# Sheet1_MPU6050.net
KiCad netlist of a schematic drawn in Altium Designer
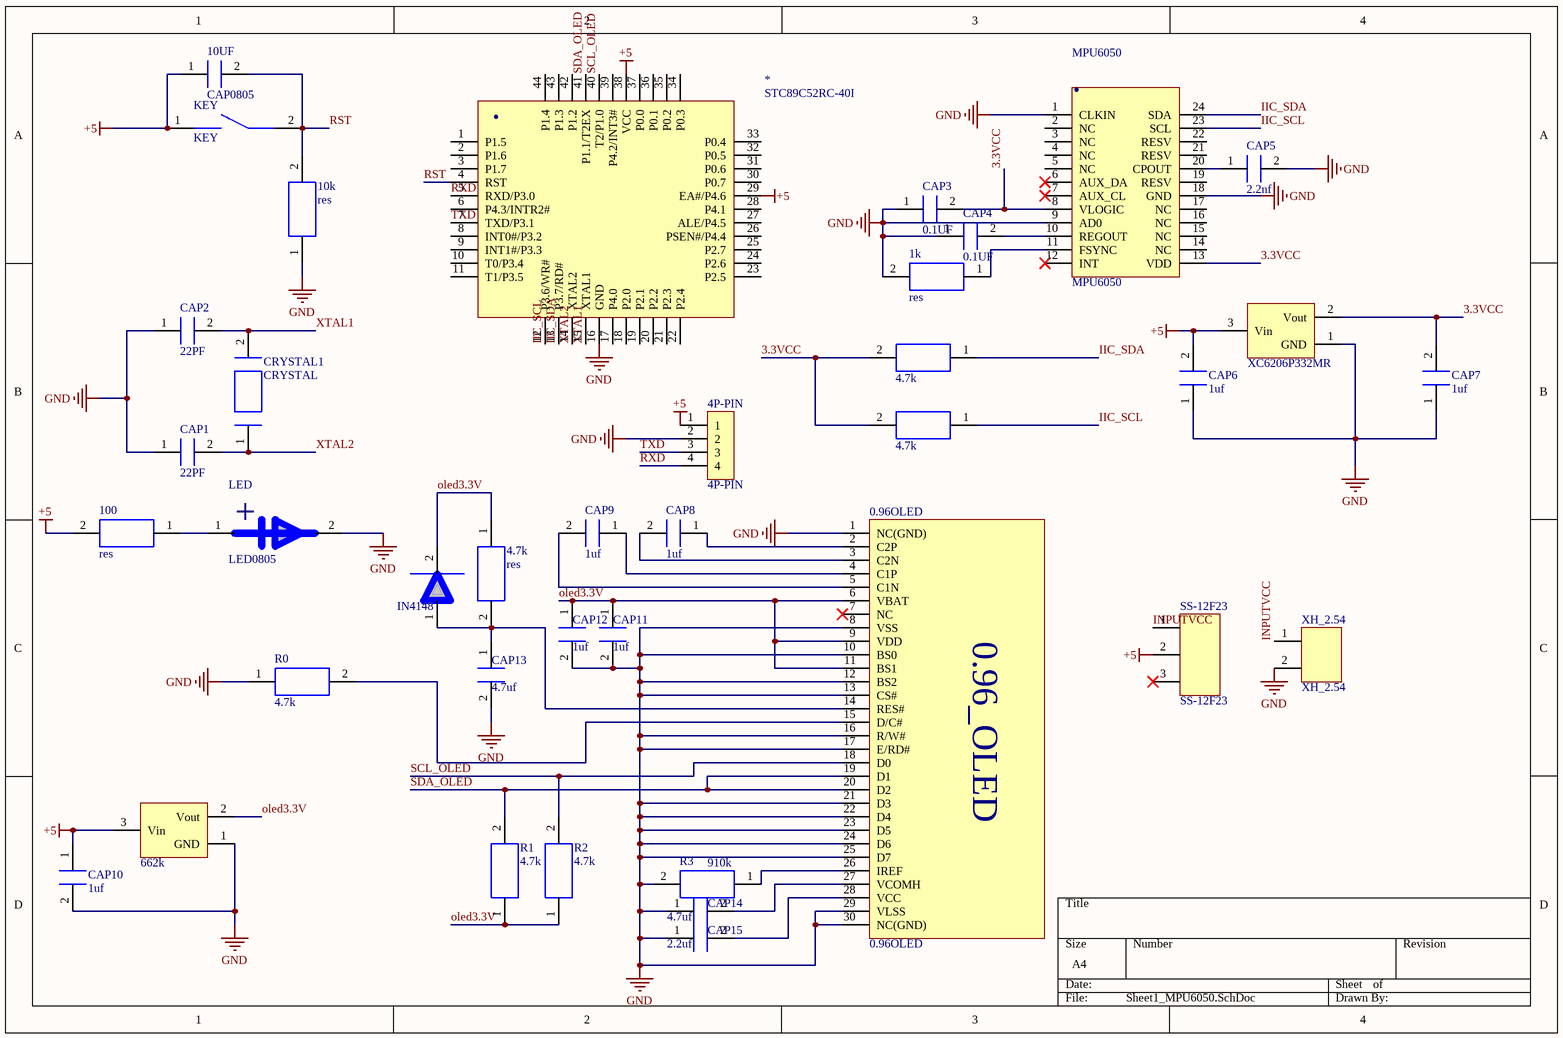
[diagram p0: Sheet1_MPU6050.SchDoc]

(export (version "E")
  (design (tool "Eeschema 10.0.6"))
  (components
    (comp (ref "*")
      (value "STC89C52RC-40I")
      (footprint "STC89C52RC-40I")
      (libsource (lib "Integrated_Library1_MPU_6050") (part "STC89C52RC-40I"))
    )
    (comp (ref "0.96OLED")
      (value "0.96OLED")
      (footprint "0.96OLED")
      (libsource (lib "Integrated_Library1_MPU_6050") (part "0.96OLED"))
    )
    (comp (ref "1k")
      (value "res")
      (footprint "RES0805")
      (libsource (lib "Integrated_Library1_MPU_6050") (part "RES0805"))
    )
    (comp (ref "4.7k")
      (value "res")
      (footprint "RES0805")
      (libsource (lib "Integrated_Library1_MPU_6050") (part "RES0805"))
    )
    (comp (ref "4P-PIN")
      (value "4P-PIN")
      (footprint "4P_PIN")
      (libsource (lib "Integrated_Library1_MPU_6050") (part "4P-PIN"))
    )
    (comp (ref "10k")
      (value "res")
      (footprint "RES0805")
      (libsource (lib "Integrated_Library1_MPU_6050") (part "RES0805"))
    )
    (comp (ref "10UF")
      (value "CAP0805")
      (footprint "CAP0805")
      (libsource (lib "Integrated_Library1_MPU_6050") (part "CAP0805"))
    )
    (comp (ref "100")
      (value "res")
      (footprint "RES0805")
      (libsource (lib "Integrated_Library1_MPU_6050") (part "RES0805"))
    )
    (comp (ref "662k")
      (value "662k")
      (footprint "XC6206P332MR")
      (libsource (lib "Integrated_Library1_MPU_6050") (part "XC6206P332MR"))
    )
    (comp (ref "CAP1")
      (value "22PF")
      (footprint "CAP0805")
      (libsource (lib "Integrated_Library1_MPU_6050") (part "CAP0805"))
    )
    (comp (ref "CAP2")
      (value "22PF")
      (footprint "CAP0805")
      (libsource (lib "Integrated_Library1_MPU_6050") (part "CAP0805"))
    )
    (comp (ref "CAP3")
      (value "0.1UF")
      (footprint "CAP0805")
      (libsource (lib "Integrated_Library1_MPU_6050") (part "CAP0805"))
    )
    (comp (ref "CAP4")
      (value "0.1UF")
      (footprint "CAP0805")
      (libsource (lib "Integrated_Library1_MPU_6050") (part "CAP0805"))
    )
    (comp (ref "CAP5")
      (value "2.2nf")
      (footprint "CAP0805")
      (libsource (lib "Integrated_Library1_MPU_6050") (part "CAP0805"))
    )
    (comp (ref "CAP6")
      (value "1uf")
      (footprint "CAP0805")
      (libsource (lib "Integrated_Library1_MPU_6050") (part "CAP0805"))
    )
    (comp (ref "CAP7")
      (value "1uf")
      (footprint "CAP0805")
      (libsource (lib "Integrated_Library1_MPU_6050") (part "CAP0805"))
    )
    (comp (ref "CAP8")
      (value "1uf")
      (footprint "CAP0805")
      (libsource (lib "Integrated_Library1_MPU_6050") (part "CAP0805"))
    )
    (comp (ref "CAP9")
      (value "1uf")
      (footprint "CAP0805")
      (libsource (lib "Integrated_Library1_MPU_6050") (part "CAP0805"))
    )
    (comp (ref "CAP10")
      (value "1uf")
      (footprint "CAP0805")
      (libsource (lib "Integrated_Library1_MPU_6050") (part "CAP0805"))
    )
    (comp (ref "CAP11")
      (value "1uf")
      (footprint "CAP0805")
      (libsource (lib "Integrated_Library1_MPU_6050") (part "CAP0805"))
    )
    (comp (ref "CAP12")
      (value "1uf")
      (footprint "CAP0805")
      (libsource (lib "Integrated_Library1_MPU_6050") (part "CAP0805"))
    )
    (comp (ref "CAP13")
      (value "4.7uf")
      (footprint "CAP0805")
      (libsource (lib "Integrated_Library1_MPU_6050") (part "CAP0805"))
    )
    (comp (ref "CAP14")
      (value "4.7uf")
      (footprint "CAP0805")
      (libsource (lib "Integrated_Library1_MPU_6050") (part "CAP0805"))
    )
    (comp (ref "CAP15")
      (value "2.2uf")
      (footprint "CAP0805")
      (libsource (lib "Integrated_Library1_MPU_6050") (part "CAP0805"))
    )
    (comp (ref "CRYSTAL1")
      (value "CRYSTAL")
      (footprint "晶振")
      (libsource (lib "Integrated_Library1_MPU_6050") (part "晶振"))
    )
    (comp (ref "IN4148")
      (value "IN4148")
      (footprint "IN4148")
      (libsource (lib "Integrated_Library1_MPU_6050") (part "IN4148"))
    )
    (comp (ref "KEY")
      (value "KEY")
      (footprint "KEY")
      (libsource (lib "Integrated_Library1_MPU_6050") (part "KEY"))
    )
    (comp (ref "LED")
      (value "LED0805")
      (footprint "LED0805")
      (libsource (lib "Integrated_Library1_MPU_6050") (part "LED0805"))
    )
    (comp (ref "MPU6050")
      (value "MPU6050")
      (footprint "MPU6050")
      (libsource (lib "Integrated_Library1_MPU_6050") (part "MPU6050"))
    )
    (comp (ref "R0")
      (value "4.7k")
      (footprint "RES0805")
      (libsource (lib "Integrated_Library1_MPU_6050") (part "RES0805"))
    )
    (comp (ref "R1")
      (value "4.7k")
      (footprint "RES0805")
      (libsource (lib "Integrated_Library1_MPU_6050") (part "RES0805"))
    )
    (comp (ref "R2")
      (value "4.7k")
      (footprint "RES0805")
      (libsource (lib "Integrated_Library1_MPU_6050") (part "RES0805"))
    )
    (comp (ref "R3")
      (value "910k")
      (footprint "RES0805")
      (libsource (lib "Integrated_Library1_MPU_6050") (part "RES0805"))
    )
    (comp (ref "res1")
      (value "4.7k")
      (footprint "RES0805")
      (libsource (lib "Integrated_Library1_MPU_6050") (part "RES0805"))
    )
    (comp (ref "res2")
      (value "4.7k")
      (footprint "RES0805")
      (libsource (lib "Integrated_Library1_MPU_6050") (part "RES0805"))
    )
    (comp (ref "SS-12F23")
      (value "SS-12F23")
      (footprint "拨动开关SS-12F23")
      (libsource (lib "Integrated_Library1_MPU_6050") (part "拨动开关SS-12F23"))
    )
    (comp (ref "XC6206P332MR")
      (value "XC6206P332MR")
      (footprint "XC6206P332MR")
      (libsource (lib "Integrated_Library1_MPU_6050") (part "XC6206P332MR"))
    )
    (comp (ref "XH_2.54")
      (value "XH_2.54")
      (footprint "XH_2.54")
      (libsource (lib "Integrated_Library1_MPU_6050") (part "XH_2.54"))
    )
  )
  (nets
    (net (code "1") (name "+5") (class "Default")
      (node (ref "*") (pin "29") (pinfunction "EA#/P4.6_29") (pintype "passive"))
      (node (ref "*") (pin "38") (pinfunction "VCC_38") (pintype "passive"))
      (node (ref "100") (pin "2") (pinfunction "2_2") (pintype "passive"))
      (node (ref "10UF") (pin "1") (pinfunction "1_1") (pintype "passive"))
      (node (ref "4P-PIN") (pin "1") (pinfunction "1_1") (pintype "passive"))
      (node (ref "662k") (pin "3") (pinfunction "Vin_3") (pintype "passive"))
      (node (ref "CAP10") (pin "1") (pinfunction "1_1") (pintype "passive"))
      (node (ref "CAP6") (pin "2") (pinfunction "2_2") (pintype "passive"))
      (node (ref "KEY") (pin "1") (pinfunction "1_1") (pintype "passive"))
      (node (ref "SS-12F23") (pin "2") (pinfunction "2_2") (pintype "passive"))
      (node (ref "XC6206P332MR") (pin "3") (pinfunction "Vin_3") (pintype "passive"))
    )
    (net (code "2") (name "/3.3VCC") (class "Default")
      (node (ref "CAP3") (pin "2") (pinfunction "2_2") (pintype "passive"))
      (node (ref "CAP7") (pin "2") (pinfunction "2_2") (pintype "passive"))
      (node (ref "MPU6050") (pin "13") (pinfunction "VDD_13") (pintype "passive"))
      (node (ref "MPU6050") (pin "8") (pinfunction "VLOGIC_8") (pintype "passive"))
      (node (ref "XC6206P332MR") (pin "2") (pinfunction "Vout_2") (pintype "passive"))
      (node (ref "res1") (pin "2") (pinfunction "2_2") (pintype "passive"))
      (node (ref "res2") (pin "2") (pinfunction "2_2") (pintype "passive"))
    )
    (net (code "3") (name "/IIC_SCL") (class "Default")
      (node (ref "*") (pin "12") (pinfunction "P3.6/WR#_12") (pintype "passive"))
      (node (ref "MPU6050") (pin "23") (pinfunction "SCL_23") (pintype "passive"))
      (node (ref "res2") (pin "1") (pinfunction "1_1") (pintype "passive"))
    )
    (net (code "4") (name "/IIC_SDA") (class "Default")
      (node (ref "*") (pin "13") (pinfunction "P3.7/RD#_13") (pintype "passive"))
      (node (ref "MPU6050") (pin "24") (pinfunction "SDA_24") (pintype "passive"))
      (node (ref "res1") (pin "1") (pinfunction "1_1") (pintype "passive"))
    )
    (net (code "5") (name "/INPUTVCC") (class "Default")
      (node (ref "SS-12F23") (pin "1") (pinfunction "1_1") (pintype "passive"))
      (node (ref "XH_2.54") (pin "1") (pinfunction "1_1") (pintype "passive"))
    )
    (net (code "6") (name "/RST") (class "Default")
      (node (ref "*") (pin "4") (pinfunction "RST_4") (pintype "passive"))
      (node (ref "10UF") (pin "2") (pinfunction "2_2") (pintype "passive"))
      (node (ref "10k") (pin "2") (pinfunction "2_2") (pintype "passive"))
      (node (ref "KEY") (pin "2") (pinfunction "2_2") (pintype "passive"))
    )
    (net (code "7") (name "/RXD") (class "Default")
      (node (ref "*") (pin "5") (pinfunction "RXD/P3.0_5") (pintype "passive"))
      (node (ref "4P-PIN") (pin "4") (pinfunction "4_4") (pintype "passive"))
    )
    (net (code "8") (name "/SCL_OLED") (class "Default")
      (node (ref "*") (pin "40") (pinfunction "T2/P1.0_40") (pintype "passive"))
      (node (ref "0.96OLED") (pin "18") (pinfunction "D0_18") (pintype "passive"))
      (node (ref "R2") (pin "2") (pinfunction "2_2") (pintype "passive"))
    )
    (net (code "9") (name "/SDA_OLED") (class "Default")
      (node (ref "*") (pin "41") (pinfunction "P1.1/T2EX_41") (pintype "passive"))
      (node (ref "0.96OLED") (pin "19") (pinfunction "D1_19") (pintype "passive"))
      (node (ref "0.96OLED") (pin "20") (pinfunction "D2_20") (pintype "passive"))
      (node (ref "R1") (pin "2") (pinfunction "2_2") (pintype "passive"))
    )
    (net (code "10") (name "/TXD") (class "Default")
      (node (ref "*") (pin "7") (pinfunction "TXD/P3.1_7") (pintype "passive"))
      (node (ref "4P-PIN") (pin "3") (pinfunction "3_3") (pintype "passive"))
    )
    (net (code "11") (name "/XTAL1") (class "Default")
      (node (ref "*") (pin "15") (pinfunction "XTAL1_15") (pintype "passive"))
      (node (ref "CAP2") (pin "2") (pinfunction "2_2") (pintype "passive"))
      (node (ref "CRYSTAL1") (pin "2") (pinfunction "2_2") (pintype "passive"))
    )
    (net (code "12") (name "/XTAL2") (class "Default")
      (node (ref "*") (pin "14") (pinfunction "XTAL2_14") (pintype "passive"))
      (node (ref "CAP1") (pin "2") (pinfunction "2_2") (pintype "passive"))
      (node (ref "CRYSTAL1") (pin "1") (pinfunction "1_1") (pintype "passive"))
    )
    (net (code "13") (name "/oled3.3V") (class "Default")
      (node (ref "0.96OLED") (pin "11") (pinfunction "BS1_11") (pintype "passive"))
      (node (ref "0.96OLED") (pin "6") (pinfunction "VBAT_6") (pintype "passive"))
      (node (ref "0.96OLED") (pin "9") (pinfunction "VDD_9") (pintype "passive"))
      (node (ref "4.7k") (pin "1") (pinfunction "1_1") (pintype "passive"))
      (node (ref "662k") (pin "2") (pinfunction "Vout_2") (pintype "passive"))
      (node (ref "CAP11") (pin "1") (pinfunction "1_1") (pintype "passive"))
      (node (ref "CAP12") (pin "1") (pinfunction "1_1") (pintype "passive"))
      (node (ref "IN4148") (pin "2") (pinfunction "2_2") (pintype "passive"))
      (node (ref "R1") (pin "1") (pinfunction "1_1") (pintype "passive"))
      (node (ref "R2") (pin "1") (pinfunction "1_1") (pintype "passive"))
    )
    (net (code "14") (name "GND") (class "Default")
      (node (ref "*") (pin "16") (pinfunction "GND_16") (pintype "passive"))
      (node (ref "0.96OLED") (pin "1") (pinfunction "NC(GND)_1") (pintype "passive"))
      (node (ref "0.96OLED") (pin "10") (pinfunction "BS0_10") (pintype "passive"))
      (node (ref "0.96OLED") (pin "12") (pinfunction "BS2_12") (pintype "passive"))
      (node (ref "0.96OLED") (pin "13") (pinfunction "CS#_13") (pintype "passive"))
      (node (ref "0.96OLED") (pin "16") (pinfunction "R/W#_16") (pintype "passive"))
      (node (ref "0.96OLED") (pin "17") (pinfunction "E/RD#_17") (pintype "passive"))
      (node (ref "0.96OLED") (pin "21") (pinfunction "D3_21") (pintype "passive"))
      (node (ref "0.96OLED") (pin "22") (pinfunction "D4_22") (pintype "passive"))
      (node (ref "0.96OLED") (pin "23") (pinfunction "D5_23") (pintype "passive"))
      (node (ref "0.96OLED") (pin "24") (pinfunction "D6_24") (pintype "passive"))
      (node (ref "0.96OLED") (pin "25") (pinfunction "D7_25") (pintype "passive"))
      (node (ref "0.96OLED") (pin "29") (pinfunction "VLSS_29") (pintype "passive"))
      (node (ref "0.96OLED") (pin "30") (pinfunction "NC(GND)_30") (pintype "passive"))
      (node (ref "0.96OLED") (pin "8") (pinfunction "VSS_8") (pintype "passive"))
      (node (ref "10k") (pin "1") (pinfunction "1_1") (pintype "passive"))
      (node (ref "1k") (pin "2") (pinfunction "2_2") (pintype "passive"))
      (node (ref "4P-PIN") (pin "2") (pinfunction "2_2") (pintype "passive"))
      (node (ref "662k") (pin "1") (pinfunction "GND_1") (pintype "passive"))
      (node (ref "CAP1") (pin "1") (pinfunction "1_1") (pintype "passive"))
      (node (ref "CAP10") (pin "2") (pinfunction "2_2") (pintype "passive"))
      (node (ref "CAP11") (pin "2") (pinfunction "2_2") (pintype "passive"))
      (node (ref "CAP12") (pin "2") (pinfunction "2_2") (pintype "passive"))
      (node (ref "CAP13") (pin "2") (pinfunction "2_2") (pintype "passive"))
      (node (ref "CAP14") (pin "1") (pinfunction "1_1") (pintype "passive"))
      (node (ref "CAP15") (pin "1") (pinfunction "1_1") (pintype "passive"))
      (node (ref "CAP2") (pin "1") (pinfunction "1_1") (pintype "passive"))
      (node (ref "CAP3") (pin "1") (pinfunction "1_1") (pintype "passive"))
      (node (ref "CAP4") (pin "1") (pinfunction "1_1") (pintype "passive"))
      (node (ref "CAP5") (pin "2") (pinfunction "2_2") (pintype "passive"))
      (node (ref "CAP6") (pin "1") (pinfunction "1_1") (pintype "passive"))
      (node (ref "CAP7") (pin "1") (pinfunction "1_1") (pintype "passive"))
      (node (ref "LED") (pin "2") (pinfunction "2_2") (pintype "passive"))
      (node (ref "MPU6050") (pin "1") (pinfunction "CLKIN_1") (pintype "passive"))
      (node (ref "MPU6050") (pin "18") (pinfunction "GND_18") (pintype "passive"))
      (node (ref "MPU6050") (pin "9") (pinfunction "AD0_9") (pintype "passive"))
      (node (ref "R0") (pin "1") (pinfunction "1_1") (pintype "passive"))
      (node (ref "R3") (pin "2") (pinfunction "2_2") (pintype "passive"))
      (node (ref "XC6206P332MR") (pin "1") (pinfunction "GND_1") (pintype "passive"))
      (node (ref "XH_2.54") (pin "2") (pinfunction "2_2") (pintype "passive"))
    )
    (net (code "15") (name "Net-(0.96OLED-C1N)") (class "Default")
      (node (ref "0.96OLED") (pin "5") (pinfunction "C1N_5") (pintype "passive"))
      (node (ref "CAP9") (pin "2") (pinfunction "2_2") (pintype "passive"))
    )
    (net (code "16") (name "Net-(0.96OLED-C1P)") (class "Default")
      (node (ref "0.96OLED") (pin "4") (pinfunction "C1P_4") (pintype "passive"))
      (node (ref "CAP9") (pin "1") (pinfunction "1_1") (pintype "passive"))
    )
    (net (code "17") (name "Net-(0.96OLED-C2N)") (class "Default")
      (node (ref "0.96OLED") (pin "3") (pinfunction "C2N_3") (pintype "passive"))
      (node (ref "CAP8") (pin "2") (pinfunction "2_2") (pintype "passive"))
    )
    (net (code "18") (name "Net-(0.96OLED-C2P)") (class "Default")
      (node (ref "0.96OLED") (pin "2") (pinfunction "C2P_2") (pintype "passive"))
      (node (ref "CAP8") (pin "1") (pinfunction "1_1") (pintype "passive"))
    )
    (net (code "19") (name "Net-(0.96OLED-D{slash}C#)") (class "Default")
      (node (ref "0.96OLED") (pin "15") (pinfunction "D/C#_15") (pintype "passive"))
      (node (ref "R0") (pin "2") (pinfunction "2_2") (pintype "passive"))
    )
    (net (code "20") (name "Net-(0.96OLED-IREF)") (class "Default")
      (node (ref "0.96OLED") (pin "26") (pinfunction "IREF_26") (pintype "passive"))
      (node (ref "R3") (pin "1") (pinfunction "1_1") (pintype "passive"))
    )
    (net (code "21") (name "Net-(0.96OLED-RES#)") (class "Default")
      (node (ref "0.96OLED") (pin "14") (pinfunction "RES#_14") (pintype "passive"))
      (node (ref "4.7k") (pin "2") (pinfunction "2_2") (pintype "passive"))
      (node (ref "CAP13") (pin "1") (pinfunction "1_1") (pintype "passive"))
      (node (ref "IN4148") (pin "1") (pinfunction "1_1") (pintype "passive"))
    )
    (net (code "22") (name "Net-(0.96OLED-VCC)") (class "Default")
      (node (ref "0.96OLED") (pin "28") (pinfunction "VCC_28") (pintype "passive"))
      (node (ref "CAP15") (pin "2") (pinfunction "2_2") (pintype "passive"))
    )
    (net (code "23") (name "Net-(0.96OLED-VCOMH)") (class "Default")
      (node (ref "0.96OLED") (pin "27") (pinfunction "VCOMH_27") (pintype "passive"))
      (node (ref "CAP14") (pin "2") (pinfunction "2_2") (pintype "passive"))
    )
    (net (code "24") (name "Net-(100-Pad1)") (class "Default")
      (node (ref "100") (pin "1") (pinfunction "1_1") (pintype "passive"))
      (node (ref "LED") (pin "1") (pinfunction "1_1") (pintype "passive"))
    )
    (net (code "25") (name "Net-(MPU6050-CPOUT)") (class "Default")
      (node (ref "CAP5") (pin "1") (pinfunction "1_1") (pintype "passive"))
      (node (ref "MPU6050") (pin "20") (pinfunction "CPOUT_20") (pintype "passive"))
    )
    (net (code "26") (name "Net-(MPU6050-FSYNC)") (class "Default")
      (node (ref "1k") (pin "1") (pinfunction "1_1") (pintype "passive"))
      (node (ref "MPU6050") (pin "11") (pinfunction "FSYNC_11") (pintype "passive"))
    )
    (net (code "27") (name "Net-(MPU6050-REGOUT)") (class "Default")
      (node (ref "CAP4") (pin "2") (pinfunction "2_2") (pintype "passive"))
      (node (ref "MPU6050") (pin "10") (pinfunction "REGOUT_10") (pintype "passive"))
    )
    (net (code "28") (name "unconnected-(*-ALE{slash}P4.5-Pad27)") (class "Default")
      (node (ref "*") (pin "27") (pinfunction "ALE/P4.5_27") (pintype "passive"))
    )
    (net (code "29") (name "unconnected-(*-INT0#{slash}P3.2-Pad8)") (class "Default")
      (node (ref "*") (pin "8") (pinfunction "INT0#/P3.2_8") (pintype "passive"))
    )
    (net (code "30") (name "unconnected-(*-INT1#{slash}P3.3-Pad9)") (class "Default")
      (node (ref "*") (pin "9") (pinfunction "INT1#/P3.3_9") (pintype "passive"))
    )
    (net (code "31") (name "unconnected-(*-P0.0-Pad37)") (class "Default")
      (node (ref "*") (pin "37") (pinfunction "P0.0_37") (pintype "passive"))
    )
    (net (code "32") (name "unconnected-(*-P0.1-Pad36)") (class "Default")
      (node (ref "*") (pin "36") (pinfunction "P0.1_36") (pintype "passive"))
    )
    (net (code "33") (name "unconnected-(*-P0.2-Pad35)") (class "Default")
      (node (ref "*") (pin "35") (pinfunction "P0.2_35") (pintype "passive"))
    )
    (net (code "34") (name "unconnected-(*-P0.3-Pad34)") (class "Default")
      (node (ref "*") (pin "34") (pinfunction "P0.3_34") (pintype "passive"))
    )
    (net (code "35") (name "unconnected-(*-P0.4-Pad33)") (class "Default")
      (node (ref "*") (pin "33") (pinfunction "P0.4_33") (pintype "passive"))
    )
    (net (code "36") (name "unconnected-(*-P0.5-Pad32)") (class "Default")
      (node (ref "*") (pin "32") (pinfunction "P0.5_32") (pintype "passive"))
    )
    (net (code "37") (name "unconnected-(*-P0.6-Pad31)") (class "Default")
      (node (ref "*") (pin "31") (pinfunction "P0.6_31") (pintype "passive"))
    )
    (net (code "38") (name "unconnected-(*-P0.7-Pad30)") (class "Default")
      (node (ref "*") (pin "30") (pinfunction "P0.7_30") (pintype "passive"))
    )
    (net (code "39") (name "unconnected-(*-P1.2-Pad42)") (class "Default")
      (node (ref "*") (pin "42") (pinfunction "P1.2_42") (pintype "passive"))
    )
    (net (code "40") (name "unconnected-(*-P1.3-Pad43)") (class "Default")
      (node (ref "*") (pin "43") (pinfunction "P1.3_43") (pintype "passive"))
    )
    (net (code "41") (name "unconnected-(*-P1.4-Pad44)") (class "Default")
      (node (ref "*") (pin "44") (pinfunction "P1.4_44") (pintype "passive"))
    )
    (net (code "42") (name "unconnected-(*-P1.5-Pad1)") (class "Default")
      (node (ref "*") (pin "1") (pinfunction "P1.5_1") (pintype "passive"))
    )
    (net (code "43") (name "unconnected-(*-P1.6-Pad2)") (class "Default")
      (node (ref "*") (pin "2") (pinfunction "P1.6_2") (pintype "passive"))
    )
    (net (code "44") (name "unconnected-(*-P1.7-Pad3)") (class "Default")
      (node (ref "*") (pin "3") (pinfunction "P1.7_3") (pintype "passive"))
    )
    (net (code "45") (name "unconnected-(*-P2.0-Pad18)") (class "Default")
      (node (ref "*") (pin "18") (pinfunction "P2.0_18") (pintype "passive"))
    )
    (net (code "46") (name "unconnected-(*-P2.1-Pad19)") (class "Default")
      (node (ref "*") (pin "19") (pinfunction "P2.1_19") (pintype "passive"))
    )
    (net (code "47") (name "unconnected-(*-P2.2-Pad20)") (class "Default")
      (node (ref "*") (pin "20") (pinfunction "P2.2_20") (pintype "passive"))
    )
    (net (code "48") (name "unconnected-(*-P2.3-Pad21)") (class "Default")
      (node (ref "*") (pin "21") (pinfunction "P2.3_21") (pintype "passive"))
    )
    (net (code "49") (name "unconnected-(*-P2.4-Pad22)") (class "Default")
      (node (ref "*") (pin "22") (pinfunction "P2.4_22") (pintype "passive"))
    )
    (net (code "50") (name "unconnected-(*-P2.5-Pad23)") (class "Default")
      (node (ref "*") (pin "23") (pinfunction "P2.5_23") (pintype "passive"))
    )
    (net (code "51") (name "unconnected-(*-P2.6-Pad24)") (class "Default")
      (node (ref "*") (pin "24") (pinfunction "P2.6_24") (pintype "passive"))
    )
    (net (code "52") (name "unconnected-(*-P2.7-Pad25)") (class "Default")
      (node (ref "*") (pin "25") (pinfunction "P2.7_25") (pintype "passive"))
    )
    (net (code "53") (name "unconnected-(*-P4.0-Pad17)") (class "Default")
      (node (ref "*") (pin "17") (pinfunction "P4.0_17") (pintype "passive"))
    )
    (net (code "54") (name "unconnected-(*-P4.1-Pad28)") (class "Default")
      (node (ref "*") (pin "28") (pinfunction "P4.1_28") (pintype "passive"))
    )
    (net (code "55") (name "unconnected-(*-P4.2{slash}INT3#-Pad39)") (class "Default")
      (node (ref "*") (pin "39") (pinfunction "P4.2/INT3#_39") (pintype "passive"))
    )
    (net (code "56") (name "unconnected-(*-P4.3{slash}INTR2#-Pad6)") (class "Default")
      (node (ref "*") (pin "6") (pinfunction "P4.3/INTR2#_6") (pintype "passive"))
    )
    (net (code "57") (name "unconnected-(*-PSEN#{slash}P4.4-Pad26)") (class "Default")
      (node (ref "*") (pin "26") (pinfunction "PSEN#/P4.4_26") (pintype "passive"))
    )
    (net (code "58") (name "unconnected-(*-T0{slash}P3.4-Pad10)") (class "Default")
      (node (ref "*") (pin "10") (pinfunction "T0/P3.4_10") (pintype "passive"))
    )
    (net (code "59") (name "unconnected-(*-T1{slash}P3.5-Pad11)") (class "Default")
      (node (ref "*") (pin "11") (pinfunction "T1/P3.5_11") (pintype "passive"))
    )
    (net (code "60") (name "unconnected-(0.96OLED-NC-Pad7)") (class "Default")
      (node (ref "0.96OLED") (pin "7") (pinfunction "NC_7") (pintype "passive+no_connect"))
    )
    (net (code "61") (name "unconnected-(MPU6050-AUX_CL-Pad7)") (class "Default")
      (node (ref "MPU6050") (pin "7") (pinfunction "AUX_CL_7") (pintype "passive+no_connect"))
    )
    (net (code "62") (name "unconnected-(MPU6050-AUX_DA-Pad6)") (class "Default")
      (node (ref "MPU6050") (pin "6") (pinfunction "AUX_DA_6") (pintype "passive+no_connect"))
    )
    (net (code "63") (name "unconnected-(MPU6050-INT-Pad12)") (class "Default")
      (node (ref "MPU6050") (pin "12") (pinfunction "INT_12") (pintype "passive+no_connect"))
    )
    (net (code "64") (name "unconnected-(MPU6050-NC-Pad2)") (class "Default")
      (node (ref "MPU6050") (pin "2") (pinfunction "NC_2") (pintype "passive"))
    )
    (net (code "65") (name "unconnected-(MPU6050-NC-Pad3)") (class "Default")
      (node (ref "MPU6050") (pin "3") (pinfunction "NC_3") (pintype "passive"))
    )
    (net (code "66") (name "unconnected-(MPU6050-NC-Pad4)") (class "Default")
      (node (ref "MPU6050") (pin "4") (pinfunction "NC_4") (pintype "passive"))
    )
    (net (code "67") (name "unconnected-(MPU6050-NC-Pad5)") (class "Default")
      (node (ref "MPU6050") (pin "5") (pinfunction "NC_5") (pintype "passive"))
    )
    (net (code "68") (name "unconnected-(MPU6050-NC-Pad14)") (class "Default")
      (node (ref "MPU6050") (pin "14") (pinfunction "NC_14") (pintype "passive"))
    )
    (net (code "69") (name "unconnected-(MPU6050-NC-Pad15)") (class "Default")
      (node (ref "MPU6050") (pin "15") (pinfunction "NC_15") (pintype "passive"))
    )
    (net (code "70") (name "unconnected-(MPU6050-NC-Pad16)") (class "Default")
      (node (ref "MPU6050") (pin "16") (pinfunction "NC_16") (pintype "passive"))
    )
    (net (code "71") (name "unconnected-(MPU6050-NC-Pad17)") (class "Default")
      (node (ref "MPU6050") (pin "17") (pinfunction "NC_17") (pintype "passive"))
    )
    (net (code "72") (name "unconnected-(MPU6050-RESV-Pad19)") (class "Default")
      (node (ref "MPU6050") (pin "19") (pinfunction "RESV_19") (pintype "passive"))
    )
    (net (code "73") (name "unconnected-(MPU6050-RESV-Pad21)") (class "Default")
      (node (ref "MPU6050") (pin "21") (pinfunction "RESV_21") (pintype "passive"))
    )
    (net (code "74") (name "unconnected-(MPU6050-RESV-Pad22)") (class "Default")
      (node (ref "MPU6050") (pin "22") (pinfunction "RESV_22") (pintype "passive"))
    )
    (net (code "75") (name "unconnected-(SS-12F23-Pad3)") (class "Default")
      (node (ref "SS-12F23") (pin "3") (pinfunction "3_3") (pintype "passive+no_connect"))
    )
  )
)
